# clap_schematic.net
KiCad netlist of a schematic drawn in Altium Designer
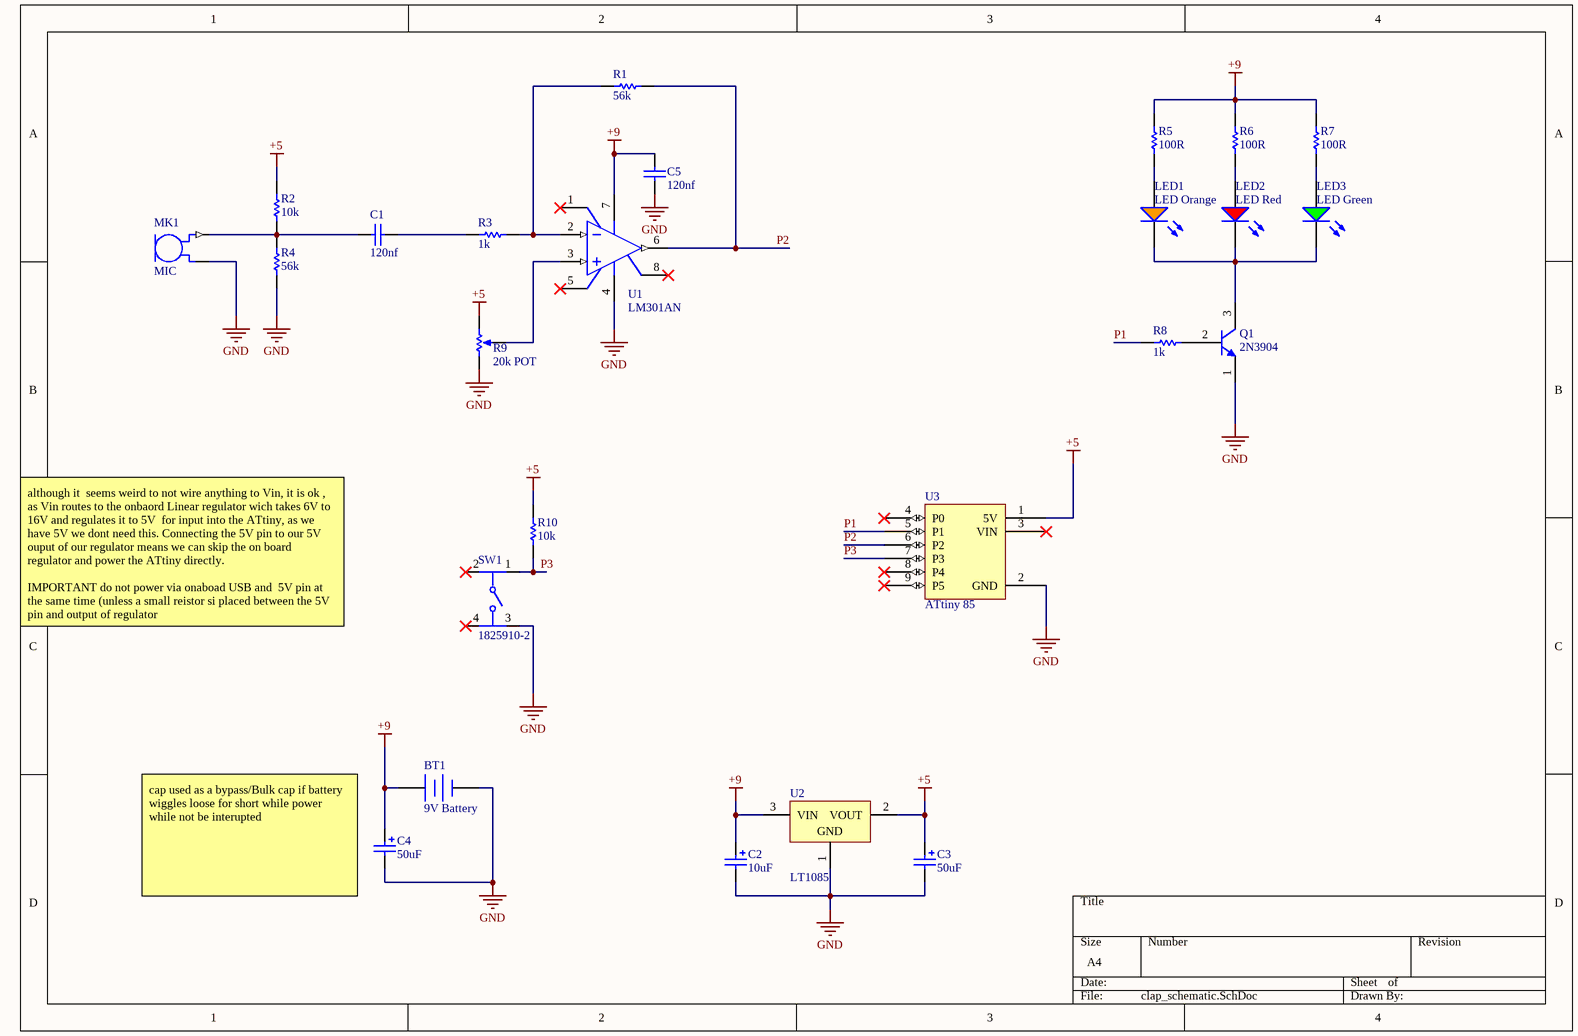
[diagram p0: clap_schematic.SchDoc]

(export (version "E")
  (design (tool "Eeschema 10.0.6"))
  (components
    (comp (ref "BT1")
      (value "9V Battery")
      (footprint "Battery")
      (fields (field (name "PUBLISHER") "Altium Limited"))
      (libsource (lib "clap") (part "9V Battery"))
    )
    (comp (ref "C1")
      (value "120nf")
      (footprint "C322C334M5U5TA7301")
      (description "120nF Capacitor")
      (fields (field (name "PUBLISHER") "Altium Limited"))
      (libsource (lib "clap") (part "120nF"))
    )
    (comp (ref "C2")
      (value "10uF")
      (footprint "Ecap_Axial_2mm_5mm")
      (description "10uF electrolytic capacitor")
      (fields (field (name "PUBLISHER") "Altium Limited"))
      (libsource (lib "clap") (part "10uF"))
    )
    (comp (ref "C3")
      (value "50uF")
      (footprint "Ecap_Axial_2mm_6.5mm")
      (description "50uF electrolytic capacitor")
      (fields (field (name "PUBLISHER") "Altium Limited"))
      (libsource (lib "clap") (part "50uF"))
    )
    (comp (ref "C4")
      (value "50uF")
      (footprint "Ecap_Axial_2mm_6.5mm")
      (description "50uF electrolytic capacitor")
      (fields (field (name "PUBLISHER") "Altium Limited"))
      (libsource (lib "clap") (part "50uF"))
    )
    (comp (ref "C5")
      (value "120nf")
      (footprint "C322C334M5U5TA7301")
      (description "120nF Capacitor")
      (fields (field (name "PUBLISHER") "Altium Limited"))
      (libsource (lib "clap") (part "120nF"))
    )
    (comp (ref "LED1")
      (value "LED Orange")
      (footprint "LED 3D")
      (description "Orange LED")
      (fields (field (name "MANUFACTURER") "Vishay"))
      (libsource (lib "clap") (part "LED Orange"))
    )
    (comp (ref "LED2")
      (value "LED Red")
      (footprint "LED 3D")
      (description "Red LED")
      (fields (field (name "MANUFACTURER") "Vishay"))
      (libsource (lib "clap") (part "LED Red"))
    )
    (comp (ref "LED3")
      (value "LED Green")
      (footprint "LED 3D")
      (description "Green LED")
      (fields (field (name "MANUFACTURER") "Vishay"))
      (libsource (lib "clap") (part "LED Green"))
    )
    (comp (ref "MK1")
      (value "MIC")
      (footprint "MIC")
      (description "CMA Series 9.7 mm Electret Condenser Omni-Directional Pin Mount 3 V Microphone")
      (fields (field (name "MP") "CMA-4544PF-W"))
      (libsource (lib "clap") (part "MIC"))
    )
    (comp (ref "Q1")
      (value "2N3904")
      (footprint "2N3904 (straight)")
      (description "2N3904 NPN General-Purpose Amplifier, 40 V VCEO, 0.2 A, -55 to 150 degC, 2-Pin TO-92, RoHS, Bulk")
      (fields (field (name "MANUFACTURER") "FairchildSemiconductor"))
      (libsource (lib "clap") (part "2N3904"))
    )
    (comp (ref "R1")
      (value "56k")
      (footprint "Res through hole")
      (description "56k Resistor")
      (fields (field (name "PUBLISHER") "Altium Limited"))
      (libsource (lib "clap") (part "56k"))
    )
    (comp (ref "R2")
      (value "10k")
      (footprint "Res through hole")
      (description "10k Resistor")
      (fields (field (name "PUBLISHER") "Altium Limited"))
      (libsource (lib "clap") (part "10k"))
    )
    (comp (ref "R3")
      (value "1k")
      (footprint "Res through hole")
      (description "1k Resistor")
      (fields (field (name "PUBLISHER") "Altium Limited"))
      (libsource (lib "clap") (part "1k"))
    )
    (comp (ref "R4")
      (value "56k")
      (footprint "Res through hole")
      (description "56k Resistor")
      (fields (field (name "PUBLISHER") "Altium Limited"))
      (libsource (lib "clap") (part "56k"))
    )
    (comp (ref "R5")
      (value "100R")
      (footprint "Res through hole")
      (description "Resistor")
      (fields (field (name "PUBLISHER") "Altium Limited"))
      (libsource (lib "clap") (part "100R"))
    )
    (comp (ref "R6")
      (value "100R")
      (footprint "Res through hole")
      (description "Resistor")
      (fields (field (name "PUBLISHER") "Altium Limited"))
      (libsource (lib "clap") (part "100R"))
    )
    (comp (ref "R7")
      (value "100R")
      (footprint "Res through hole")
      (description "Resistor")
      (fields (field (name "PUBLISHER") "Altium Limited"))
      (libsource (lib "clap") (part "100R"))
    )
    (comp (ref "R8")
      (value "1k")
      (footprint "Res through hole")
      (description "1k Resistor")
      (fields (field (name "PUBLISHER") "Altium Limited"))
      (libsource (lib "clap") (part "1k"))
    )
    (comp (ref "R9")
      (value "20k POT")
      (footprint "TRIM_3296W-1-203RLF")
      (description "20k Potentiometer")
      (fields (field (name "PUBLISHER") "Altium Limited"))
      (libsource (lib "clap") (part "20k POT"))
    )
    (comp (ref "R10")
      (value "10k")
      (footprint "Res through hole")
      (description "10k Resistor")
      (fields (field (name "PUBLISHER") "Altium Limited"))
      (libsource (lib "clap") (part "10k"))
    )
    (comp (ref "SW1")
      (value "1825910-2")
      (footprint "FP-1825910-2-0")
      (description "Switch Tactile Round Button PC Pins 0.05A 24VDC 100000Cycle 1.56N Thru-Hole")
      (fields (field (name "OCTOPART") "https://octopart.com/1825910-2-te+connectivity-42270502"))
      (libsource (lib "Altium Content Vault") (part "b8895f3f4cefb76e1819d2863dba89b"))
    )
    (comp (ref "U1")
      (value "LM301AN")
      (footprint "LM301AN")
      (description "Operational Amplifier, 8-pin MDIP")
      (fields (field (name "MANUFACTURER") "National Semiconductor"))
      (libsource (lib "clap") (part "LM301AN"))
    )
    (comp (ref "U2")
      (value "LT1085")
      (footprint "LT1085 (TO220)")
      (fields
        (field (name "MANUFACTURER") "Linear Technology")
        (field (name "PARTNUMBER") "LT1085CT-3.3#PBF")
      )
      (libsource (lib "clap") (part "LT1085"))
    )
    (comp (ref "U3")
      (value "ATtiny 85")
      (footprint "Disgispark ATtiny 85")
      (description "the mount for the digispark ATtiny 85 board")
      (libsource (lib "clap") (part "ATtiny 85"))
    )
  )
  (nets
    (net (code "1") (name "+5") (class "Default")
      (node (ref "C3") (pin "1") (pinfunction "1_1") (pintype "passive"))
      (node (ref "R10") (pin "2") (pinfunction "2_2") (pintype "passive"))
      (node (ref "R2") (pin "2") (pinfunction "2_2") (pintype "passive"))
      (node (ref "R9") (pin "3") (pinfunction "BOT_3") (pintype "passive"))
      (node (ref "U2") (pin "2") (pinfunction "VOUT_2") (pintype "power_in"))
      (node (ref "U3") (pin "1") (pinfunction "5V_1") (pintype "power_in"))
    )
    (net (code "2") (name "+9") (class "Default")
      (node (ref "BT1") (pin "1") (pinfunction "+_1") (pintype "passive"))
      (node (ref "C2") (pin "1") (pinfunction "1_1") (pintype "passive"))
      (node (ref "C4") (pin "1") (pinfunction "1_1") (pintype "passive"))
      (node (ref "C5") (pin "2") (pinfunction "2_2") (pintype "passive"))
      (node (ref "R5") (pin "2") (pinfunction "2_2") (pintype "passive"))
      (node (ref "R6") (pin "2") (pinfunction "2_2") (pintype "passive"))
      (node (ref "R7") (pin "2") (pinfunction "2_2") (pintype "passive"))
      (node (ref "U1") (pin "7") (pinfunction "V+_7") (pintype "power_in"))
      (node (ref "U2") (pin "3") (pinfunction "VIN_3") (pintype "power_in"))
    )
    (net (code "3") (name "/P1") (class "Default")
      (node (ref "R8") (pin "1") (pinfunction "1_1") (pintype "passive"))
      (node (ref "U3") (pin "5") (pinfunction "P1_5") (pintype "bidirectional"))
    )
    (net (code "4") (name "/P2") (class "Default")
      (node (ref "R1") (pin "1") (pinfunction "1_1") (pintype "passive"))
      (node (ref "U1") (pin "6") (pinfunction "OUT_6") (pintype "output"))
      (node (ref "U3") (pin "6") (pinfunction "P2_6") (pintype "bidirectional"))
    )
    (net (code "5") (name "/P3") (class "Default")
      (node (ref "R10") (pin "1") (pinfunction "1_1") (pintype "passive"))
      (node (ref "SW1") (pin "1") (pinfunction "1_1") (pintype "passive"))
      (node (ref "U3") (pin "7") (pinfunction "P3_7") (pintype "bidirectional"))
    )
    (net (code "6") (name "GND") (class "Default")
      (node (ref "BT1") (pin "2") (pinfunction "-_2") (pintype "passive"))
      (node (ref "C2") (pin "2") (pinfunction "2_2") (pintype "passive"))
      (node (ref "C3") (pin "2") (pinfunction "2_2") (pintype "passive"))
      (node (ref "C4") (pin "2") (pinfunction "2_2") (pintype "passive"))
      (node (ref "C5") (pin "1") (pinfunction "1_1") (pintype "passive"))
      (node (ref "MK1") (pin "2") (pinfunction "GND_2") (pintype "power_in"))
      (node (ref "Q1") (pin "1") (pinfunction "E_1") (pintype "passive"))
      (node (ref "R4") (pin "1") (pinfunction "1_1") (pintype "passive"))
      (node (ref "R9") (pin "1") (pinfunction "TOP_1") (pintype "passive"))
      (node (ref "SW1") (pin "3") (pinfunction "3_3") (pintype "passive"))
      (node (ref "U1") (pin "4") (pinfunction "V-_4") (pintype "power_in"))
      (node (ref "U2") (pin "1") (pinfunction "GND_1") (pintype "power_in"))
      (node (ref "U3") (pin "2") (pinfunction "GND_2") (pintype "power_in"))
    )
    (net (code "7") (name "Net-(C1-Pad2)") (class "Default")
      (node (ref "C1") (pin "2") (pinfunction "2_2") (pintype "passive"))
      (node (ref "R3") (pin "1") (pinfunction "1_1") (pintype "passive"))
    )
    (net (code "8") (name "Net-(LED1-A)") (class "Default")
      (node (ref "LED1") (pin "1") (pinfunction "A_1") (pintype "passive"))
      (node (ref "R5") (pin "1") (pinfunction "1_1") (pintype "passive"))
    )
    (net (code "9") (name "Net-(LED1-K)") (class "Default")
      (node (ref "LED1") (pin "2") (pinfunction "K_2") (pintype "passive"))
      (node (ref "LED2") (pin "2") (pinfunction "K_2") (pintype "passive"))
      (node (ref "LED3") (pin "2") (pinfunction "K_2") (pintype "passive"))
      (node (ref "Q1") (pin "3") (pinfunction "C_3") (pintype "passive"))
    )
    (net (code "10") (name "Net-(LED2-A)") (class "Default")
      (node (ref "LED2") (pin "1") (pinfunction "A_1") (pintype "passive"))
      (node (ref "R6") (pin "1") (pinfunction "1_1") (pintype "passive"))
    )
    (net (code "11") (name "Net-(LED3-A)") (class "Default")
      (node (ref "LED3") (pin "1") (pinfunction "A_1") (pintype "passive"))
      (node (ref "R7") (pin "1") (pinfunction "1_1") (pintype "passive"))
    )
    (net (code "12") (name "Net-(MK1-OUT)") (class "Default")
      (node (ref "C1") (pin "1") (pinfunction "1_1") (pintype "passive"))
      (node (ref "MK1") (pin "1") (pinfunction "OUT_1") (pintype "output"))
      (node (ref "R2") (pin "1") (pinfunction "1_1") (pintype "passive"))
      (node (ref "R4") (pin "2") (pinfunction "2_2") (pintype "passive"))
    )
    (net (code "13") (name "Net-(Q1-B)") (class "Default")
      (node (ref "Q1") (pin "2") (pinfunction "B_2") (pintype "passive"))
      (node (ref "R8") (pin "2") (pinfunction "2_2") (pintype "passive"))
    )
    (net (code "14") (name "Net-(R9-TAP)") (class "Default")
      (node (ref "R9") (pin "2") (pinfunction "TAP_2") (pintype "passive"))
      (node (ref "U1") (pin "3") (pinfunction "IN+_3") (pintype "input"))
    )
    (net (code "15") (name "Net-(U1-IN-)") (class "Default")
      (node (ref "R1") (pin "2") (pinfunction "2_2") (pintype "passive"))
      (node (ref "R3") (pin "2") (pinfunction "2_2") (pintype "passive"))
      (node (ref "U1") (pin "2") (pinfunction "IN-_2") (pintype "input"))
    )
    (net (code "16") (name "unconnected-(SW1-Pad2)") (class "Default")
      (node (ref "SW1") (pin "2") (pinfunction "2_2") (pintype "passive+no_connect"))
    )
    (net (code "17") (name "unconnected-(SW1-Pad4)") (class "Default")
      (node (ref "SW1") (pin "4") (pinfunction "4_4") (pintype "passive+no_connect"))
    )
    (net (code "18") (name "unconnected-(U1-BAL-Pad5)") (class "Default")
      (node (ref "U1") (pin "5") (pinfunction "BAL_5") (pintype "passive+no_connect"))
    )
    (net (code "19") (name "unconnected-(U1-BAL{slash}COMP-Pad1)") (class "Default")
      (node (ref "U1") (pin "1") (pinfunction "BAL/COMP_1") (pintype "passive+no_connect"))
    )
    (net (code "20") (name "unconnected-(U1-COMP-Pad8)") (class "Default")
      (node (ref "U1") (pin "8") (pinfunction "COMP_8") (pintype "passive+no_connect"))
    )
    (net (code "21") (name "unconnected-(U3-P0-Pad4)") (class "Default")
      (node (ref "U3") (pin "4") (pinfunction "P0_4") (pintype "bidirectional+no_connect"))
    )
    (net (code "22") (name "unconnected-(U3-P4-Pad8)") (class "Default")
      (node (ref "U3") (pin "8") (pinfunction "P4_8") (pintype "bidirectional+no_connect"))
    )
    (net (code "23") (name "unconnected-(U3-P5-Pad9)") (class "Default")
      (node (ref "U3") (pin "9") (pinfunction "P5_9") (pintype "bidirectional+no_connect"))
    )
    (net (code "24") (name "unconnected-(U3-VIN-Pad3)") (class "Default")
      (node (ref "U3") (pin "3") (pinfunction "VIN_3") (pintype "power_in+no_connect"))
    )
  )
)
